# Board.net
KiCad netlist of a schematic drawn in EAGLE
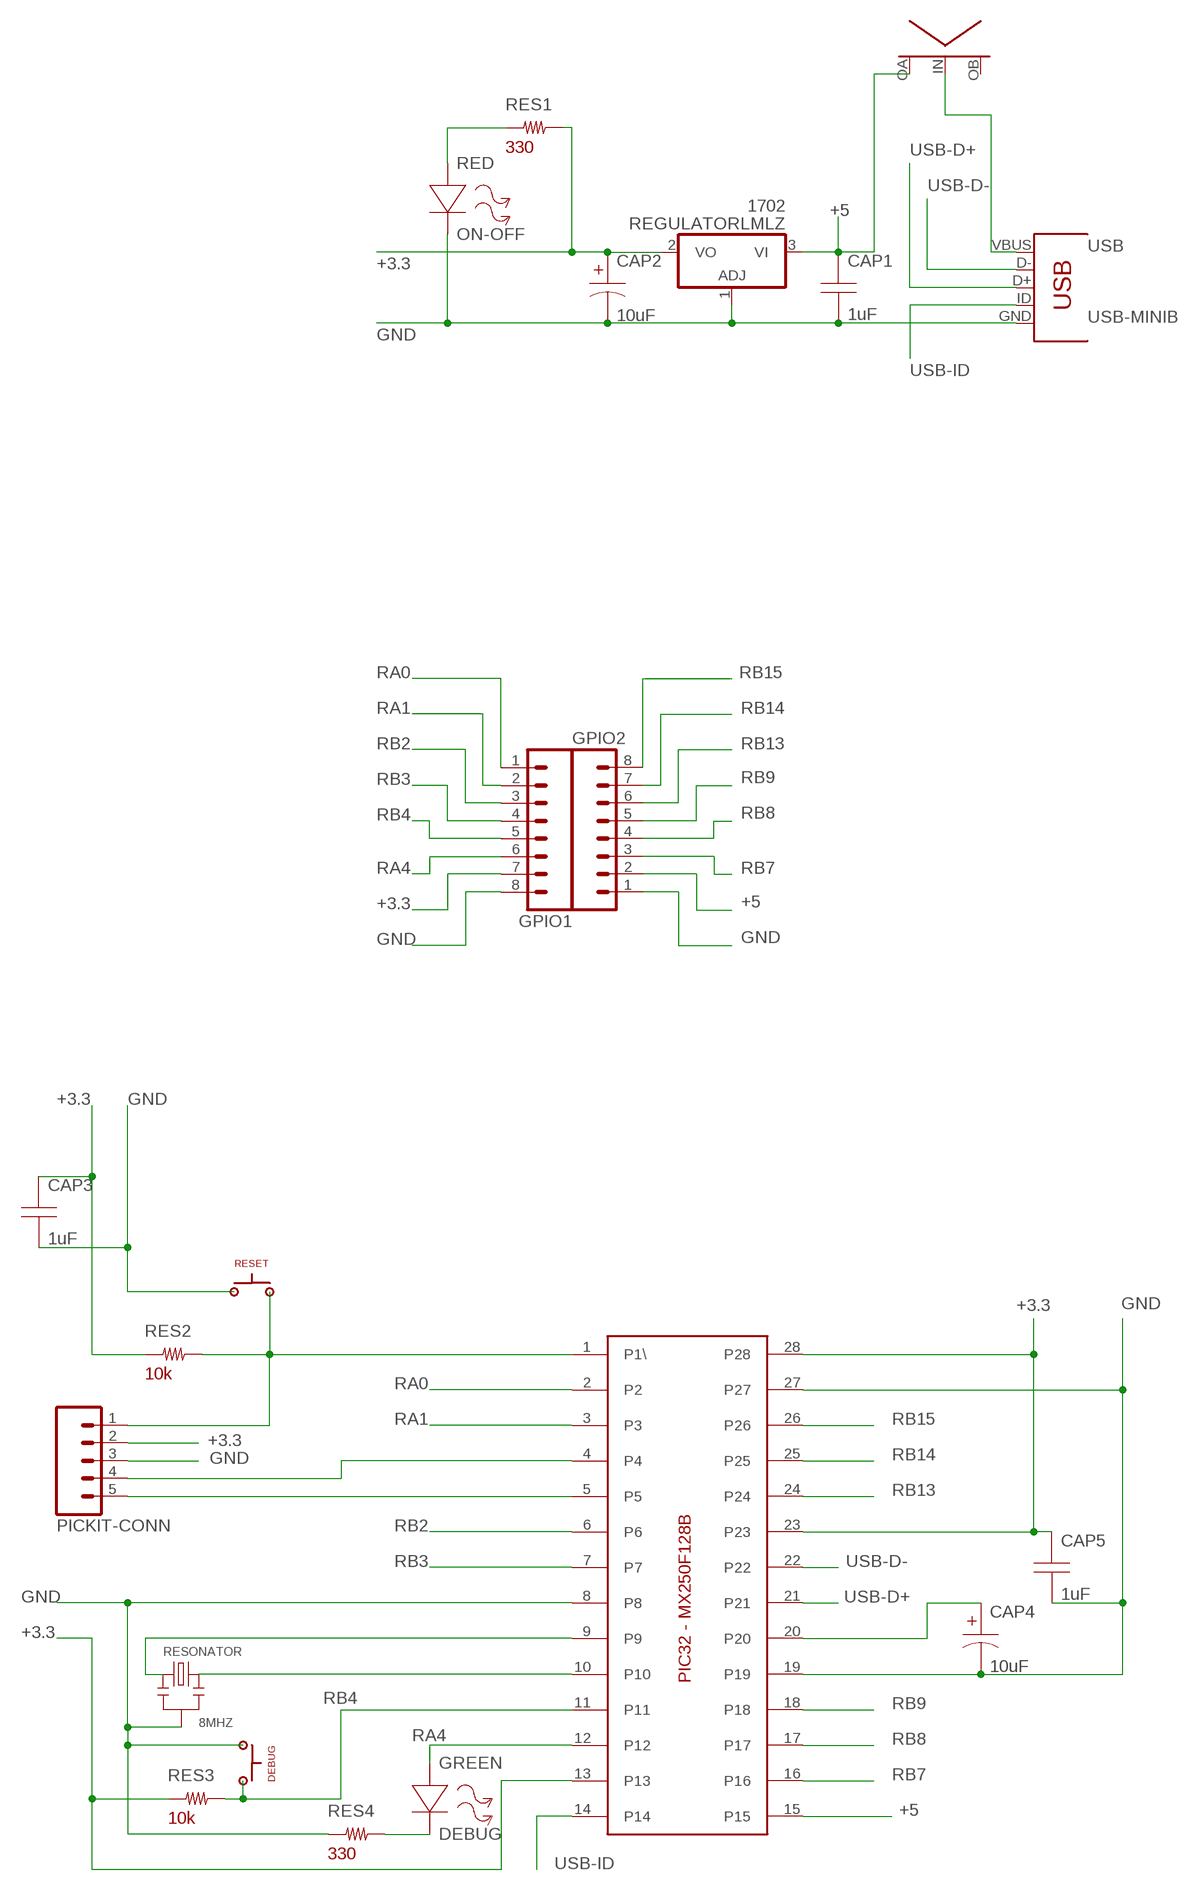
[diagram p0: schematic, sheet 1]

(export (version "E")
  (design (tool "Eeschema 10.0.6"))
  (components
    (comp (ref "1702")
      (value "REGULATORLMLZ")
      (footprint "eagle-import:TO92")
      (libsource (lib "eagle-import") (part "REGULATORLZLM"))
    )
    (comp (ref "CAP1")
      (value "1uF")
      (footprint "eagle-import:CAP-CERAMIC")
      (libsource (lib "eagle-import") (part "CAP-CERAMIC"))
    )
    (comp (ref "CAP2")
      (value "10uF")
      (footprint "eagle-import:TT2D4")
      (libsource (lib "eagle-import") (part "CAP-TANTALUM"))
    )
    (comp (ref "CAP3")
      (value "1uF")
      (footprint "eagle-import:CAP-CERAMIC")
      (libsource (lib "eagle-import") (part "CAP-CERAMIC"))
    )
    (comp (ref "CAP4")
      (value "10uF")
      (footprint "eagle-import:TT2D4")
      (libsource (lib "eagle-import") (part "CAP-TANTALUM"))
    )
    (comp (ref "CAP5")
      (value "1uF")
      (footprint "eagle-import:CAP-CERAMIC")
      (libsource (lib "eagle-import") (part "CAP-CERAMIC"))
    )
    (comp (ref "DEBUG")
      (value "BUTTON")
      (footprint "eagle-import:PUSH5")
      (libsource (lib "eagle-import") (part "BUTTON"))
    )
    (comp (ref "GPIO1")
      (value "M08")
      (footprint "eagle-import:1X08_ROUND")
      (libsource (lib "eagle-import") (part "M08"))
    )
    (comp (ref "GPIO2")
      (value "M08")
      (footprint "eagle-import:1X08_ROUND")
      (libsource (lib "eagle-import") (part "M08"))
    )
    (comp (ref "GREEN")
      (value "DEBUG")
      (footprint "eagle-import:LED")
      (libsource (lib "eagle-import") (part "LED"))
    )
    (comp (ref "PIC32-MX250F128B")
      (value "PIC32-MX250F128B")
      (footprint "eagle-import:DIL28-3")
      (libsource (lib "eagle-import") (part "PIC32-MX250F128B"))
    )
    (comp (ref "PICKIT-CONN")
      (value "CONNECTOR-5PINPTH")
      (footprint "eagle-import:CONNECTOR-5PIN")
      (libsource (lib "eagle-import") (part "CONNECTOR-5PINPTH"))
    )
    (comp (ref "RED")
      (value "ON-OFF")
      (footprint "eagle-import:LED")
      (libsource (lib "eagle-import") (part "LED"))
    )
    (comp (ref "RES1")
      (value "330")
      (footprint "eagle-import:RESISTOR-7MM")
      (libsource (lib "eagle-import") (part "RESISTOR"))
    )
    (comp (ref "RES2")
      (value "10k")
      (footprint "eagle-import:RESISTOR-7MM")
      (libsource (lib "eagle-import") (part "RESISTOR"))
    )
    (comp (ref "RES3")
      (value "10k")
      (footprint "eagle-import:RESISTOR-7MM")
      (libsource (lib "eagle-import") (part "RESISTOR"))
    )
    (comp (ref "RES4")
      (value "330")
      (footprint "eagle-import:RESISTOR-7MM")
      (libsource (lib "eagle-import") (part "RESISTOR"))
    )
    (comp (ref "RESET")
      (value "BUTTON")
      (footprint "eagle-import:PUSH5")
      (libsource (lib "eagle-import") (part "BUTTON"))
    )
    (comp (ref "RESONATOR")
      (value "8MHZ")
      (footprint "eagle-import:OSCILATOR-CRYSTAL")
      (fields (field (name "MPN") "CSTLS8M00G53Z-A0"))
      (libsource (lib "eagle-import") (part "OSCILATOR-CRYSTAL"))
    )
    (comp (ref "U$1")
      (value "SWITCH")
      (footprint "eagle-import:SWITCH")
      (libsource (lib "eagle-import") (part "SWITCH"))
    )
    (comp (ref "USB")
      (value "USB-MINIB")
      (footprint "eagle-import:USB-MB-H")
      (libsource (lib "eagle-import") (part "USB-MINIB"))
    )
  )
  (nets
    (net (code "1") (name "/+3.3") (class "Default")
      (node (ref "1702") (pin "2") (pinfunction "VO_2") (pintype "passive"))
      (node (ref "CAP2") (pin "+") (pinfunction "+_+") (pintype "passive"))
      (node (ref "CAP3") (pin "1") (pinfunction "A_1") (pintype "passive"))
      (node (ref "CAP5") (pin "1") (pinfunction "A_1") (pintype "passive"))
      (node (ref "GPIO1") (pin "7") (pinfunction "7_7") (pintype "passive"))
      (node (ref "PIC32-MX250F128B") (pin "13") (pinfunction "P13_13") (pintype "bidirectional"))
      (node (ref "PIC32-MX250F128B") (pin "23") (pinfunction "P23_23") (pintype "bidirectional"))
      (node (ref "PIC32-MX250F128B") (pin "28") (pinfunction "P28_28") (pintype "bidirectional"))
      (node (ref "PICKIT-CONN") (pin "2") (pinfunction "2_2") (pintype "passive"))
      (node (ref "RES1") (pin "2") (pinfunction "P$2_2") (pintype "bidirectional"))
      (node (ref "RES2") (pin "1") (pinfunction "P$1_1") (pintype "bidirectional"))
      (node (ref "RES3") (pin "1") (pinfunction "P$1_1") (pintype "bidirectional"))
    )
    (net (code "2") (name "/+5") (class "Default")
      (node (ref "1702") (pin "3") (pinfunction "VI_3") (pintype "input"))
      (node (ref "CAP1") (pin "1") (pinfunction "A_1") (pintype "passive"))
      (node (ref "GPIO2") (pin "2") (pinfunction "2_2") (pintype "passive"))
      (node (ref "PIC32-MX250F128B") (pin "15") (pinfunction "P15_15") (pintype "bidirectional"))
      (node (ref "U$1") (pin "OA") (pinfunction "OA_OA") (pintype "output"))
    )
    (net (code "3") (name "/GND") (class "Default")
      (node (ref "1702") (pin "1") (pinfunction "ADJ_1") (pintype "input"))
      (node (ref "CAP1") (pin "2") (pinfunction "B_2") (pintype "passive"))
      (node (ref "CAP2") (pin "-") (pinfunction "-_-") (pintype "passive"))
      (node (ref "CAP3") (pin "2") (pinfunction "B_2") (pintype "passive"))
      (node (ref "CAP4") (pin "-") (pinfunction "-_-") (pintype "passive"))
      (node (ref "CAP5") (pin "2") (pinfunction "B_2") (pintype "passive"))
      (node (ref "DEBUG") (pin "1") (pinfunction "P$1_1") (pintype "bidirectional"))
      (node (ref "GPIO1") (pin "8") (pinfunction "8_8") (pintype "passive"))
      (node (ref "GPIO2") (pin "1") (pinfunction "1_1") (pintype "passive"))
      (node (ref "PIC32-MX250F128B") (pin "19") (pinfunction "P19_19") (pintype "bidirectional"))
      (node (ref "PIC32-MX250F128B") (pin "27") (pinfunction "P27_27") (pintype "bidirectional"))
      (node (ref "PIC32-MX250F128B") (pin "8") (pinfunction "P8_8") (pintype "bidirectional"))
      (node (ref "PICKIT-CONN") (pin "3") (pinfunction "3_3") (pintype "passive"))
      (node (ref "RED") (pin "-") (pinfunction "-_-") (pintype "passive"))
      (node (ref "RES4") (pin "1") (pinfunction "P$1_1") (pintype "bidirectional"))
      (node (ref "RESET") (pin "1") (pinfunction "P$1_1") (pintype "bidirectional"))
      (node (ref "RESONATOR") (pin "2") (pinfunction "2_2") (pintype "passive"))
      (node (ref "USB") (pin "GND") (pinfunction "GND_GND") (pintype "bidirectional"))
    )
    (net (code "4") (name "/RA0") (class "Default")
      (node (ref "GPIO1") (pin "1") (pinfunction "1_1") (pintype "passive"))
      (node (ref "PIC32-MX250F128B") (pin "2") (pinfunction "P2_2") (pintype "bidirectional"))
    )
    (net (code "5") (name "/RA1") (class "Default")
      (node (ref "GPIO1") (pin "2") (pinfunction "2_2") (pintype "passive"))
      (node (ref "PIC32-MX250F128B") (pin "3") (pinfunction "P3_3") (pintype "bidirectional"))
    )
    (net (code "6") (name "/RA4") (class "Default")
      (node (ref "GPIO1") (pin "6") (pinfunction "6_6") (pintype "passive"))
      (node (ref "GREEN") (pin "+") (pinfunction "+_+") (pintype "passive"))
      (node (ref "PIC32-MX250F128B") (pin "12") (pinfunction "P12_12") (pintype "bidirectional"))
    )
    (net (code "7") (name "/RB2") (class "Default")
      (node (ref "GPIO1") (pin "3") (pinfunction "3_3") (pintype "passive"))
      (node (ref "PIC32-MX250F128B") (pin "6") (pinfunction "P6_6") (pintype "bidirectional"))
    )
    (net (code "8") (name "/RB3") (class "Default")
      (node (ref "GPIO1") (pin "4") (pinfunction "4_4") (pintype "passive"))
      (node (ref "PIC32-MX250F128B") (pin "7") (pinfunction "P7_7") (pintype "bidirectional"))
    )
    (net (code "9") (name "/RB4") (class "Default")
      (node (ref "DEBUG") (pin "2") (pinfunction "P$2_2") (pintype "bidirectional"))
      (node (ref "GPIO1") (pin "5") (pinfunction "5_5") (pintype "passive"))
      (node (ref "PIC32-MX250F128B") (pin "11") (pinfunction "P11_11") (pintype "bidirectional"))
      (node (ref "RES3") (pin "2") (pinfunction "P$2_2") (pintype "bidirectional"))
    )
    (net (code "10") (name "/RB7") (class "Default")
      (node (ref "GPIO2") (pin "3") (pinfunction "3_3") (pintype "passive"))
      (node (ref "PIC32-MX250F128B") (pin "16") (pinfunction "P16_16") (pintype "bidirectional"))
    )
    (net (code "11") (name "/RB8") (class "Default")
      (node (ref "GPIO2") (pin "4") (pinfunction "4_4") (pintype "passive"))
      (node (ref "PIC32-MX250F128B") (pin "17") (pinfunction "P17_17") (pintype "bidirectional"))
    )
    (net (code "12") (name "/RB9") (class "Default")
      (node (ref "GPIO2") (pin "5") (pinfunction "5_5") (pintype "passive"))
      (node (ref "PIC32-MX250F128B") (pin "18") (pinfunction "P18_18") (pintype "bidirectional"))
    )
    (net (code "13") (name "/RB13") (class "Default")
      (node (ref "GPIO2") (pin "6") (pinfunction "6_6") (pintype "passive"))
      (node (ref "PIC32-MX250F128B") (pin "24") (pinfunction "P24_24") (pintype "bidirectional"))
    )
    (net (code "14") (name "/RB14") (class "Default")
      (node (ref "GPIO2") (pin "7") (pinfunction "7_7") (pintype "passive"))
      (node (ref "PIC32-MX250F128B") (pin "25") (pinfunction "P25_25") (pintype "bidirectional"))
    )
    (net (code "15") (name "/RB15") (class "Default")
      (node (ref "GPIO2") (pin "8") (pinfunction "8_8") (pintype "passive"))
      (node (ref "PIC32-MX250F128B") (pin "26") (pinfunction "P26_26") (pintype "bidirectional"))
    )
    (net (code "16") (name "/USB-D+") (class "Default")
      (node (ref "PIC32-MX250F128B") (pin "21") (pinfunction "P21_21") (pintype "bidirectional"))
      (node (ref "USB") (pin "D+") (pinfunction "D+_D+") (pintype "bidirectional"))
    )
    (net (code "17") (name "/USB-D-") (class "Default")
      (node (ref "PIC32-MX250F128B") (pin "22") (pinfunction "P22_22") (pintype "bidirectional"))
      (node (ref "USB") (pin "D-") (pinfunction "D-_D-") (pintype "bidirectional"))
    )
    (net (code "18") (name "/USB-ID") (class "Default")
      (node (ref "PIC32-MX250F128B") (pin "14") (pinfunction "P14_14") (pintype "bidirectional"))
      (node (ref "USB") (pin "ID") (pinfunction "ID_ID") (pintype "bidirectional"))
    )
    (net (code "19") (name "Net-(PIC32-MX250F128B-P1\\)") (class "Default")
      (node (ref "PIC32-MX250F128B") (pin "1") (pinfunction "P1\\_1") (pintype "bidirectional"))
      (node (ref "PICKIT-CONN") (pin "1") (pinfunction "1_1") (pintype "passive"))
      (node (ref "RES2") (pin "2") (pinfunction "P$2_2") (pintype "bidirectional"))
      (node (ref "RESET") (pin "2") (pinfunction "P$2_2") (pintype "bidirectional"))
    )
    (net (code "20") (name "Net-(PIC32-MX250F128B-P4)") (class "Default")
      (node (ref "PIC32-MX250F128B") (pin "4") (pinfunction "P4_4") (pintype "bidirectional"))
      (node (ref "PICKIT-CONN") (pin "4") (pinfunction "4_4") (pintype "passive"))
    )
    (net (code "21") (name "Net-(PIC32-MX250F128B-P5)") (class "Default")
      (node (ref "PIC32-MX250F128B") (pin "5") (pinfunction "P5_5") (pintype "bidirectional"))
      (node (ref "PICKIT-CONN") (pin "5") (pinfunction "5_5") (pintype "passive"))
    )
    (net (code "22") (name "Net-(PIC32-MX250F128B-P9)") (class "Default")
      (node (ref "PIC32-MX250F128B") (pin "9") (pinfunction "P9_9") (pintype "bidirectional"))
      (node (ref "RESONATOR") (pin "1") (pinfunction "1_1") (pintype "passive"))
    )
    (net (code "23") (name "Net-(PIC32-MX250F128B-P10)") (class "Default")
      (node (ref "PIC32-MX250F128B") (pin "10") (pinfunction "P10_10") (pintype "bidirectional"))
      (node (ref "RESONATOR") (pin "3") (pinfunction "3_3") (pintype "passive"))
    )
    (net (code "24") (name "Net-(PIC32-MX250F128B-P20)") (class "Default")
      (node (ref "CAP4") (pin "+") (pinfunction "+_+") (pintype "passive"))
      (node (ref "PIC32-MX250F128B") (pin "20") (pinfunction "P20_20") (pintype "bidirectional"))
    )
    (net (code "25") (name "Net-(RES1-P$1)") (class "Default")
      (node (ref "RED") (pin "+") (pinfunction "+_+") (pintype "passive"))
      (node (ref "RES1") (pin "1") (pinfunction "P$1_1") (pintype "bidirectional"))
    )
    (net (code "26") (name "Net-(RES4-P$2)") (class "Default")
      (node (ref "GREEN") (pin "-") (pinfunction "-_-") (pintype "passive"))
      (node (ref "RES4") (pin "2") (pinfunction "P$2_2") (pintype "bidirectional"))
    )
    (net (code "27") (name "Net-(U$1-PadIN)") (class "Default")
      (node (ref "U$1") (pin "IN") (pinfunction "IN_IN") (pintype "input"))
      (node (ref "USB") (pin "VBUS") (pinfunction "VBUS_VBUS") (pintype "bidirectional"))
    )
    (net (code "28") (name "unconnected-(U$1-PadOB)") (class "Default")
      (node (ref "U$1") (pin "OB") (pinfunction "OB_OB") (pintype "output"))
    )
  )
)
